# gsm.net
KiCad netlist of a schematic drawn in Altium Designer
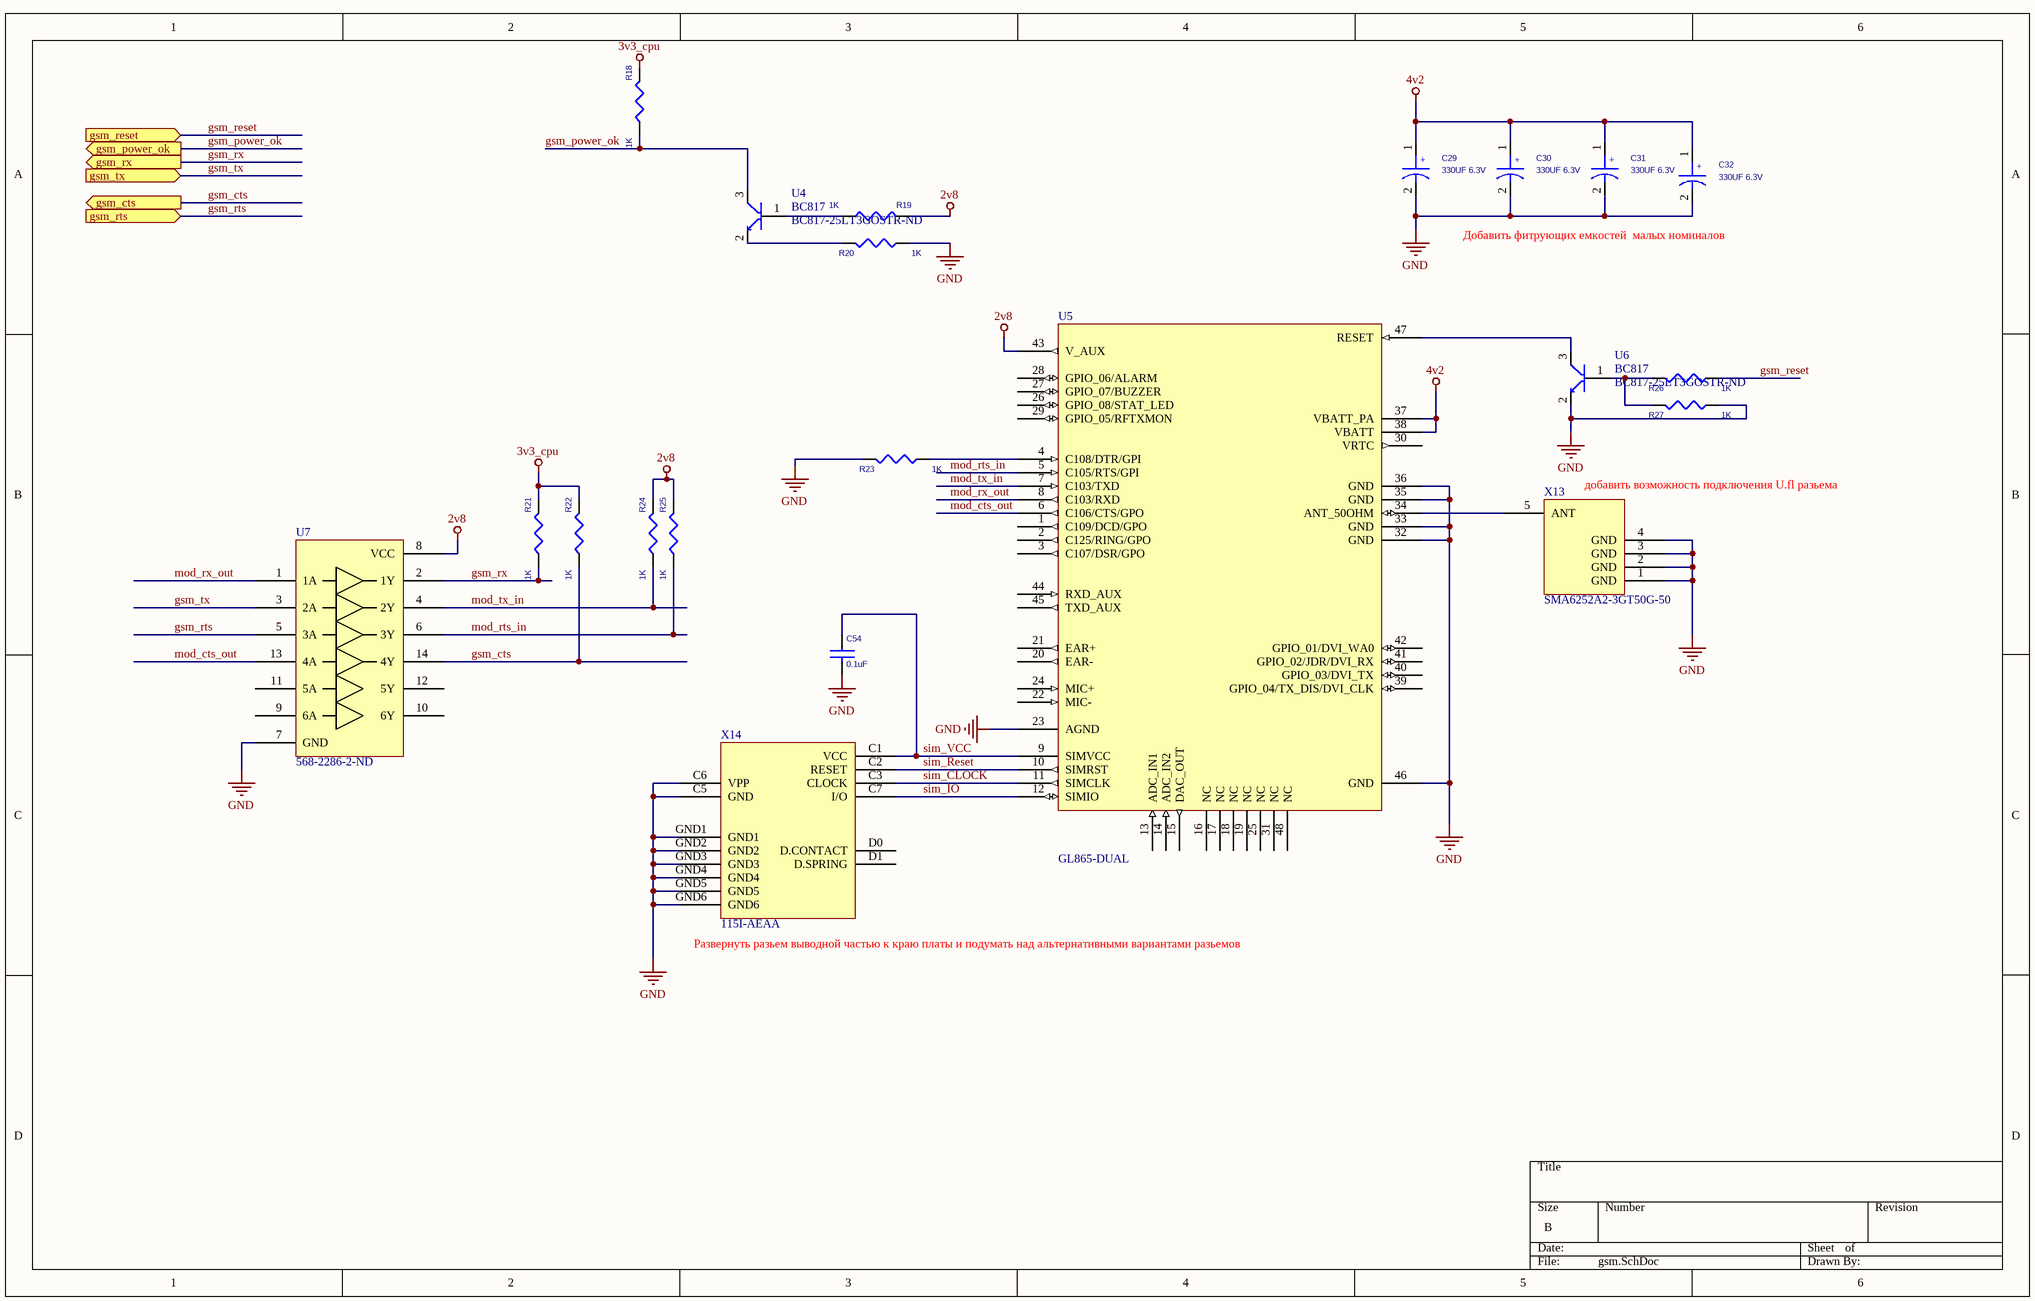
[diagram p0: gsm.SchDoc]

(export (version "E")
  (design (tool "Eeschema 10.0.6"))
  (components
    (comp (ref "C29")
      (value "330UF 6.3V")
      (footprint "CAPMP7143X31N")
      (description "CAP 330uF; 6.3V; Case: D")
      (libsource (lib "Capacitors") (part "CAP_SMD_330UF_10%"))
    )
    (comp (ref "C30")
      (value "330UF 6.3V")
      (footprint "CAPMP7143X31N")
      (description "CAP 330uF; 6.3V; Case: D")
      (libsource (lib "Capacitors") (part "CAP_SMD_330UF_10%"))
    )
    (comp (ref "C31")
      (value "330UF 6.3V")
      (footprint "CAPMP7143X31N")
      (description "CAP 330uF; 6.3V; Case: D")
      (libsource (lib "Capacitors") (part "CAP_SMD_330UF_10%"))
    )
    (comp (ref "C32")
      (value "330UF 6.3V")
      (footprint "CAPMP7143X31N")
      (description "CAP 330uF; 6.3V; Case: D")
      (libsource (lib "Capacitors") (part "CAP_SMD_330UF_10%"))
    )
    (comp (ref "C54")
      (value "0.1uF")
      (footprint "CAPC2012X09M")
      (description "CAP CER 0.1UF 25V 10% X7R 0805")
      (libsource (lib "Capacitors") (part "CAP_SMD_0.1UF_10%"))
    )
    (comp (ref "R18")
      (value "1K")
      (footprint "RESC2013X06M")
      (description "RES - 1K OHM, 5%, 1/8W, 0805 SMD")
      (libsource (lib "Resistors") (part "RES_SMD_1K_5%"))
    )
    (comp (ref "R19")
      (value "1K")
      (footprint "RESC2013X06M")
      (description "RES - 1K OHM, 5%, 1/8W, 0805 SMD")
      (libsource (lib "Resistors") (part "RES_SMD_1K_5%"))
    )
    (comp (ref "R20")
      (value "1K")
      (footprint "RESC2013X06M")
      (description "RES - 1K OHM, 5%, 1/8W, 0805 SMD")
      (libsource (lib "Resistors") (part "RES_SMD_1K_5%"))
    )
    (comp (ref "R21")
      (value "1K")
      (footprint "RESC2013X06M")
      (description "RES - 1K OHM, 5%, 1/8W, 0805 SMD")
      (libsource (lib "Resistors") (part "RES_SMD_1K_5%"))
    )
    (comp (ref "R22")
      (value "1K")
      (footprint "RESC2013X06M")
      (description "RES - 1K OHM, 5%, 1/8W, 0805 SMD")
      (libsource (lib "Resistors") (part "RES_SMD_1K_5%"))
    )
    (comp (ref "R23")
      (value "1K")
      (footprint "RESC2013X06M")
      (description "RES - 1K OHM, 5%, 1/8W, 0805 SMD")
      (libsource (lib "Resistors") (part "RES_SMD_1K_5%"))
    )
    (comp (ref "R24")
      (value "1K")
      (footprint "RESC2013X06M")
      (description "RES - 1K OHM, 5%, 1/8W, 0805 SMD")
      (libsource (lib "Resistors") (part "RES_SMD_1K_5%"))
    )
    (comp (ref "R25")
      (value "1K")
      (footprint "RESC2013X06M")
      (description "RES - 1K OHM, 5%, 1/8W, 0805 SMD")
      (libsource (lib "Resistors") (part "RES_SMD_1K_5%"))
    )
    (comp (ref "R26")
      (value "1K")
      (footprint "RESC2013X06M")
      (description "RES - 1K OHM, 5%, 1/8W, 0805 SMD")
      (libsource (lib "Resistors") (part "RES_SMD_1K_5%"))
    )
    (comp (ref "R27")
      (value "1K")
      (footprint "RESC2013X06M")
      (description "RES - 1K OHM, 5%, 1/8W, 0805 SMD")
      (libsource (lib "Resistors") (part "RES_SMD_1K_5%"))
    )
    (comp (ref "U4")
      (value "BC817")
      (footprint "SOT95P237X111-3N_SOT-23")
      (fields (field (name "SUPPLIER PART NUMBER 1") "BC817-25LT3GOSTR-ND"))
      (libsource (lib "TruthEar") (part "BC817"))
    )
    (comp (ref "U5")
      (value "GL865-DUAL")
      (footprint "GL865_FOOT")
      (libsource (lib "TruthEar") (part "GL865-DUAL"))
    )
    (comp (ref "U6")
      (value "BC817")
      (footprint "SOT95P237X111-3N_SOT-23")
      (fields (field (name "SUPPLIER PART NUMBER 1") "BC817-25LT3GOSTR-ND"))
      (libsource (lib "TruthEar") (part "BC817"))
    )
    (comp (ref "U7")
      (value "74LVC07A")
      (footprint "TSOP127P600X145-14N")
      (fields (field (name "SUPPLIER PART NUMBER 1") "568-2286-2-ND"))
      (libsource (lib "TruthEar") (part "74LVC07A"))
    )
    (comp (ref "X13")
      (value "SMA6252A2-3GT50G-50")
      (footprint "SMA6252A2-3GT50G-50")
      (libsource (lib "Connectors") (part "SMA_CONN"))
    )
    (comp (ref "X14")
      (value "115I-AEAA")
      (footprint "115I-AEAA")
      (libsource (lib "Connectors") (part "SIM_CARD_115I-AEAA"))
    )
  )
  (nets
    (net (code "1") (name "/gsm_cts") (class "Default")
      (node (ref "R22") (pin "1") (pinfunction "1_1") (pintype "passive"))
      (node (ref "U7") (pin "14") (pinfunction "4Y_14") (pintype "power_in"))
    )
    (net (code "2") (name "/gsm_power_ok") (class "Default")
      (node (ref "R18") (pin "1") (pinfunction "1_1") (pintype "passive"))
      (node (ref "U4") (pin "3") (pinfunction "C_3") (pintype "passive"))
    )
    (net (code "3") (name "/gsm_reset") (class "Default")
      (node (ref "R26") (pin "1") (pinfunction "1_1") (pintype "passive"))
    )
    (net (code "4") (name "/gsm_rts") (class "Default")
      (node (ref "U7") (pin "5") (pinfunction "3A_5") (pintype "power_in"))
    )
    (net (code "5") (name "/gsm_rx") (class "Default")
      (node (ref "R21") (pin "1") (pinfunction "1_1") (pintype "passive"))
      (node (ref "U7") (pin "2") (pinfunction "1Y_2") (pintype "power_in"))
    )
    (net (code "6") (name "/gsm_tx") (class "Default")
      (node (ref "U7") (pin "3") (pinfunction "2A_3") (pintype "power_in"))
    )
    (net (code "7") (name "/mod_cts_out") (class "Default")
      (node (ref "U5") (pin "6") (pinfunction "C106/CTS/GPO_6") (pintype "output"))
      (node (ref "U7") (pin "13") (pinfunction "4A_13") (pintype "power_in"))
    )
    (net (code "8") (name "/mod_rts_in") (class "Default")
      (node (ref "R25") (pin "1") (pinfunction "1_1") (pintype "passive"))
      (node (ref "U5") (pin "5") (pinfunction "C105/RTS/GPI_5") (pintype "input"))
      (node (ref "U7") (pin "6") (pinfunction "3Y_6") (pintype "power_in"))
    )
    (net (code "9") (name "/mod_rx_out") (class "Default")
      (node (ref "U5") (pin "8") (pinfunction "C103/RXD_8") (pintype "output"))
      (node (ref "U7") (pin "1") (pinfunction "1A_1") (pintype "power_in"))
    )
    (net (code "10") (name "/mod_tx_in") (class "Default")
      (node (ref "R24") (pin "1") (pinfunction "1_1") (pintype "passive"))
      (node (ref "U5") (pin "7") (pinfunction "C103/TXD_7") (pintype "input"))
      (node (ref "U7") (pin "4") (pinfunction "2Y_4") (pintype "power_in"))
    )
    (net (code "11") (name "/sim_CLOCK") (class "Default")
      (node (ref "U5") (pin "11") (pinfunction "SIMCLK_11") (pintype "output"))
      (node (ref "X14") (pin "C3") (pinfunction "CLOCK_C3") (pintype "passive"))
    )
    (net (code "12") (name "/sim_IO") (class "Default")
      (node (ref "U5") (pin "12") (pinfunction "SIMIO_12") (pintype "bidirectional"))
      (node (ref "X14") (pin "C7") (pinfunction "I/O_C7") (pintype "passive"))
    )
    (net (code "13") (name "/sim_Reset") (class "Default")
      (node (ref "U5") (pin "10") (pinfunction "SIMRST_10") (pintype "output"))
      (node (ref "X14") (pin "C2") (pinfunction "RESET_C2") (pintype "passive"))
    )
    (net (code "14") (name "/sim_VCC") (class "Default")
      (node (ref "C54") (pin "1") (pinfunction "1_1") (pintype "passive"))
      (node (ref "U5") (pin "9") (pinfunction "SIMVCC_9") (pintype "passive"))
      (node (ref "X14") (pin "C1") (pinfunction "VCC_C1") (pintype "passive"))
    )
    (net (code "15") (name "2v8") (class "Default")
      (node (ref "R19") (pin "2") (pinfunction "2_2") (pintype "passive"))
      (node (ref "R24") (pin "2") (pinfunction "2_2") (pintype "passive"))
      (node (ref "R25") (pin "2") (pinfunction "2_2") (pintype "passive"))
      (node (ref "U5") (pin "43") (pinfunction "V_AUX_43") (pintype "output"))
      (node (ref "U7") (pin "8") (pinfunction "VCC_8") (pintype "power_in"))
    )
    (net (code "16") (name "3v3_cpu") (class "Default")
      (node (ref "R18") (pin "2") (pinfunction "2_2") (pintype "passive"))
      (node (ref "R21") (pin "2") (pinfunction "2_2") (pintype "passive"))
      (node (ref "R22") (pin "2") (pinfunction "2_2") (pintype "passive"))
    )
    (net (code "17") (name "4v2") (class "Default")
      (node (ref "C29") (pin "1") (pinfunction "1_1") (pintype "passive"))
      (node (ref "C30") (pin "1") (pinfunction "1_1") (pintype "passive"))
      (node (ref "C31") (pin "1") (pinfunction "1_1") (pintype "passive"))
      (node (ref "C32") (pin "1") (pinfunction "1_1") (pintype "passive"))
      (node (ref "U5") (pin "37") (pinfunction "VBATT_PA_37") (pintype "passive"))
      (node (ref "U5") (pin "38") (pinfunction "VBATT_38") (pintype "passive"))
    )
    (net (code "18") (name "GND") (class "Default")
      (node (ref "C29") (pin "2") (pinfunction "2_2") (pintype "passive"))
      (node (ref "C30") (pin "2") (pinfunction "2_2") (pintype "passive"))
      (node (ref "C31") (pin "2") (pinfunction "2_2") (pintype "passive"))
      (node (ref "C32") (pin "2") (pinfunction "2_2") (pintype "passive"))
      (node (ref "C54") (pin "2") (pinfunction "2_2") (pintype "passive"))
      (node (ref "R20") (pin "1") (pinfunction "1_1") (pintype "passive"))
      (node (ref "R23") (pin "2") (pinfunction "2_2") (pintype "passive"))
      (node (ref "R27") (pin "1") (pinfunction "1_1") (pintype "passive"))
      (node (ref "U5") (pin "23") (pinfunction "AGND_23") (pintype "passive"))
      (node (ref "U5") (pin "32") (pinfunction "GND_32") (pintype "passive"))
      (node (ref "U5") (pin "33") (pinfunction "GND_33") (pintype "passive"))
      (node (ref "U5") (pin "35") (pinfunction "GND_35") (pintype "passive"))
      (node (ref "U5") (pin "36") (pinfunction "GND_36") (pintype "passive"))
      (node (ref "U5") (pin "46") (pinfunction "GND_46") (pintype "passive"))
      (node (ref "U6") (pin "2") (pinfunction "E_2") (pintype "passive"))
      (node (ref "U7") (pin "7") (pinfunction "GND_7") (pintype "power_in"))
      (node (ref "X13") (pin "1") (pinfunction "GND_1") (pintype "passive"))
      (node (ref "X13") (pin "2") (pinfunction "GND_2") (pintype "passive"))
      (node (ref "X13") (pin "3") (pinfunction "GND_3") (pintype "passive"))
      (node (ref "X13") (pin "4") (pinfunction "GND_4") (pintype "passive"))
      (node (ref "X14") (pin "C5") (pinfunction "GND_C5") (pintype "passive"))
      (node (ref "X14") (pin "C6") (pinfunction "VPP_C6") (pintype "passive"))
      (node (ref "X14") (pin "GND1") (pinfunction "GND1_GND1") (pintype "passive"))
      (node (ref "X14") (pin "GND2") (pinfunction "GND2_GND2") (pintype "passive"))
      (node (ref "X14") (pin "GND3") (pinfunction "GND3_GND3") (pintype "passive"))
      (node (ref "X14") (pin "GND4") (pinfunction "GND4_GND4") (pintype "passive"))
      (node (ref "X14") (pin "GND5") (pinfunction "GND5_GND5") (pintype "passive"))
      (node (ref "X14") (pin "GND6") (pinfunction "GND6_GND6") (pintype "passive"))
    )
    (net (code "19") (name "Net-(U4-B)") (class "Default")
      (node (ref "R19") (pin "1") (pinfunction "1_1") (pintype "passive"))
      (node (ref "U4") (pin "1") (pinfunction "B_1") (pintype "passive"))
    )
    (net (code "20") (name "Net-(U4-E)") (class "Default")
      (node (ref "R20") (pin "2") (pinfunction "2_2") (pintype "passive"))
      (node (ref "U4") (pin "2") (pinfunction "E_2") (pintype "passive"))
    )
    (net (code "21") (name "Net-(U5-ANT_50OHM)") (class "Default")
      (node (ref "U5") (pin "34") (pinfunction "ANT_50OHM_34") (pintype "bidirectional"))
      (node (ref "X13") (pin "5") (pinfunction "ANT_5") (pintype "passive"))
    )
    (net (code "22") (name "Net-(U5-C108{slash}DTR{slash}GPI)") (class "Default")
      (node (ref "R23") (pin "1") (pinfunction "1_1") (pintype "passive"))
      (node (ref "U5") (pin "4") (pinfunction "C108/DTR/GPI_4") (pintype "input"))
    )
    (net (code "23") (name "Net-(U5-RESET)") (class "Default")
      (node (ref "U5") (pin "47") (pinfunction "RESET_47") (pintype "input"))
      (node (ref "U6") (pin "3") (pinfunction "C_3") (pintype "passive"))
    )
    (net (code "24") (name "Net-(U6-B)") (class "Default")
      (node (ref "R26") (pin "2") (pinfunction "2_2") (pintype "passive"))
      (node (ref "R27") (pin "2") (pinfunction "2_2") (pintype "passive"))
      (node (ref "U6") (pin "1") (pinfunction "B_1") (pintype "passive"))
    )
    (net (code "25") (name "unconnected-(U5-ADC_IN1-Pad13)") (class "Default")
      (node (ref "U5") (pin "13") (pinfunction "ADC_IN1_13") (pintype "input"))
    )
    (net (code "26") (name "unconnected-(U5-ADC_IN2-Pad14)") (class "Default")
      (node (ref "U5") (pin "14") (pinfunction "ADC_IN2_14") (pintype "input"))
    )
    (net (code "27") (name "unconnected-(U5-C107{slash}DSR{slash}GPO-Pad3)") (class "Default")
      (node (ref "U5") (pin "3") (pinfunction "C107/DSR/GPO_3") (pintype "output"))
    )
    (net (code "28") (name "unconnected-(U5-C109{slash}DCD{slash}GPO-Pad1)") (class "Default")
      (node (ref "U5") (pin "1") (pinfunction "C109/DCD/GPO_1") (pintype "output"))
    )
    (net (code "29") (name "unconnected-(U5-C125{slash}RING{slash}GPO-Pad2)") (class "Default")
      (node (ref "U5") (pin "2") (pinfunction "C125/RING/GPO_2") (pintype "output"))
    )
    (net (code "30") (name "unconnected-(U5-DAC_OUT-Pad15)") (class "Default")
      (node (ref "U5") (pin "15") (pinfunction "DAC_OUT_15") (pintype "output"))
    )
    (net (code "31") (name "unconnected-(U5-EAR+-Pad21)") (class "Default")
      (node (ref "U5") (pin "21") (pinfunction "EAR+_21") (pintype "output"))
    )
    (net (code "32") (name "unconnected-(U5-EAR--Pad20)") (class "Default")
      (node (ref "U5") (pin "20") (pinfunction "EAR-_20") (pintype "output"))
    )
    (net (code "33") (name "unconnected-(U5-GPIO_01{slash}DVI_WA0-Pad42)") (class "Default")
      (node (ref "U5") (pin "42") (pinfunction "GPIO_01/DVI_WA0_42") (pintype "bidirectional"))
    )
    (net (code "34") (name "unconnected-(U5-GPIO_02{slash}JDR{slash}DVI_RX-Pad41)") (class "Default")
      (node (ref "U5") (pin "41") (pinfunction "GPIO_02/JDR/DVI_RX_41") (pintype "bidirectional"))
    )
    (net (code "35") (name "unconnected-(U5-GPIO_03{slash}DVI_TX-Pad40)") (class "Default")
      (node (ref "U5") (pin "40") (pinfunction "GPIO_03/DVI_TX_40") (pintype "bidirectional"))
    )
    (net (code "36") (name "unconnected-(U5-GPIO_04{slash}TX_DIS{slash}DVI_CLK-Pad39)") (class "Default")
      (node (ref "U5") (pin "39") (pinfunction "GPIO_04/TX_DIS/DVI_CLK_39") (pintype "bidirectional"))
    )
    (net (code "37") (name "unconnected-(U5-GPIO_05{slash}RFTXMON-Pad29)") (class "Default")
      (node (ref "U5") (pin "29") (pinfunction "GPIO_05/RFTXMON_29") (pintype "bidirectional"))
    )
    (net (code "38") (name "unconnected-(U5-GPIO_06{slash}ALARM-Pad28)") (class "Default")
      (node (ref "U5") (pin "28") (pinfunction "GPIO_06/ALARM_28") (pintype "bidirectional"))
    )
    (net (code "39") (name "unconnected-(U5-GPIO_07{slash}BUZZER-Pad27)") (class "Default")
      (node (ref "U5") (pin "27") (pinfunction "GPIO_07/BUZZER_27") (pintype "bidirectional"))
    )
    (net (code "40") (name "unconnected-(U5-GPIO_08{slash}STAT_LED-Pad26)") (class "Default")
      (node (ref "U5") (pin "26") (pinfunction "GPIO_08/STAT_LED_26") (pintype "bidirectional"))
    )
    (net (code "41") (name "unconnected-(U5-MIC+-Pad24)") (class "Default")
      (node (ref "U5") (pin "24") (pinfunction "MIC+_24") (pintype "input"))
    )
    (net (code "42") (name "unconnected-(U5-MIC--Pad22)") (class "Default")
      (node (ref "U5") (pin "22") (pinfunction "MIC-_22") (pintype "input"))
    )
    (net (code "43") (name "unconnected-(U5-NC-Pad16)") (class "Default")
      (node (ref "U5") (pin "16") (pinfunction "NC_16") (pintype "passive"))
    )
    (net (code "44") (name "unconnected-(U5-NC-Pad17)") (class "Default")
      (node (ref "U5") (pin "17") (pinfunction "NC_17") (pintype "passive"))
    )
    (net (code "45") (name "unconnected-(U5-NC-Pad18)") (class "Default")
      (node (ref "U5") (pin "18") (pinfunction "NC_18") (pintype "passive"))
    )
    (net (code "46") (name "unconnected-(U5-NC-Pad19)") (class "Default")
      (node (ref "U5") (pin "19") (pinfunction "NC_19") (pintype "passive"))
    )
    (net (code "47") (name "unconnected-(U5-NC-Pad25)") (class "Default")
      (node (ref "U5") (pin "25") (pinfunction "NC_25") (pintype "passive"))
    )
    (net (code "48") (name "unconnected-(U5-NC-Pad31)") (class "Default")
      (node (ref "U5") (pin "31") (pinfunction "NC_31") (pintype "passive"))
    )
    (net (code "49") (name "unconnected-(U5-NC-Pad48)") (class "Default")
      (node (ref "U5") (pin "48") (pinfunction "NC_48") (pintype "passive"))
    )
    (net (code "50") (name "unconnected-(U5-RXD_AUX-Pad44)") (class "Default")
      (node (ref "U5") (pin "44") (pinfunction "RXD_AUX_44") (pintype "input"))
    )
    (net (code "51") (name "unconnected-(U5-TXD_AUX-Pad45)") (class "Default")
      (node (ref "U5") (pin "45") (pinfunction "TXD_AUX_45") (pintype "output"))
    )
    (net (code "52") (name "unconnected-(U5-VRTC-Pad30)") (class "Default")
      (node (ref "U5") (pin "30") (pinfunction "VRTC_30") (pintype "output"))
    )
    (net (code "53") (name "unconnected-(U7-5A-Pad11)") (class "Default")
      (node (ref "U7") (pin "11") (pinfunction "5A_11") (pintype "power_in"))
    )
    (net (code "54") (name "unconnected-(U7-5Y-Pad12)") (class "Default")
      (node (ref "U7") (pin "12") (pinfunction "5Y_12") (pintype "power_in"))
    )
    (net (code "55") (name "unconnected-(U7-6A-Pad9)") (class "Default")
      (node (ref "U7") (pin "9") (pinfunction "6A_9") (pintype "power_in"))
    )
    (net (code "56") (name "unconnected-(U7-6Y-Pad10)") (class "Default")
      (node (ref "U7") (pin "10") (pinfunction "6Y_10") (pintype "power_in"))
    )
    (net (code "57") (name "unconnected-(X14-D.CONTACT-PadD0)") (class "Default")
      (node (ref "X14") (pin "D0") (pinfunction "D.CONTACT_D0") (pintype "passive"))
    )
    (net (code "58") (name "unconnected-(X14-D.SPRING-PadD1)") (class "Default")
      (node (ref "X14") (pin "D1") (pinfunction "D.SPRING_D1") (pintype "passive"))
    )
  )
)
